# COMM_2022-13-02.net
KiCad netlist of a schematic drawn in Altium Designer
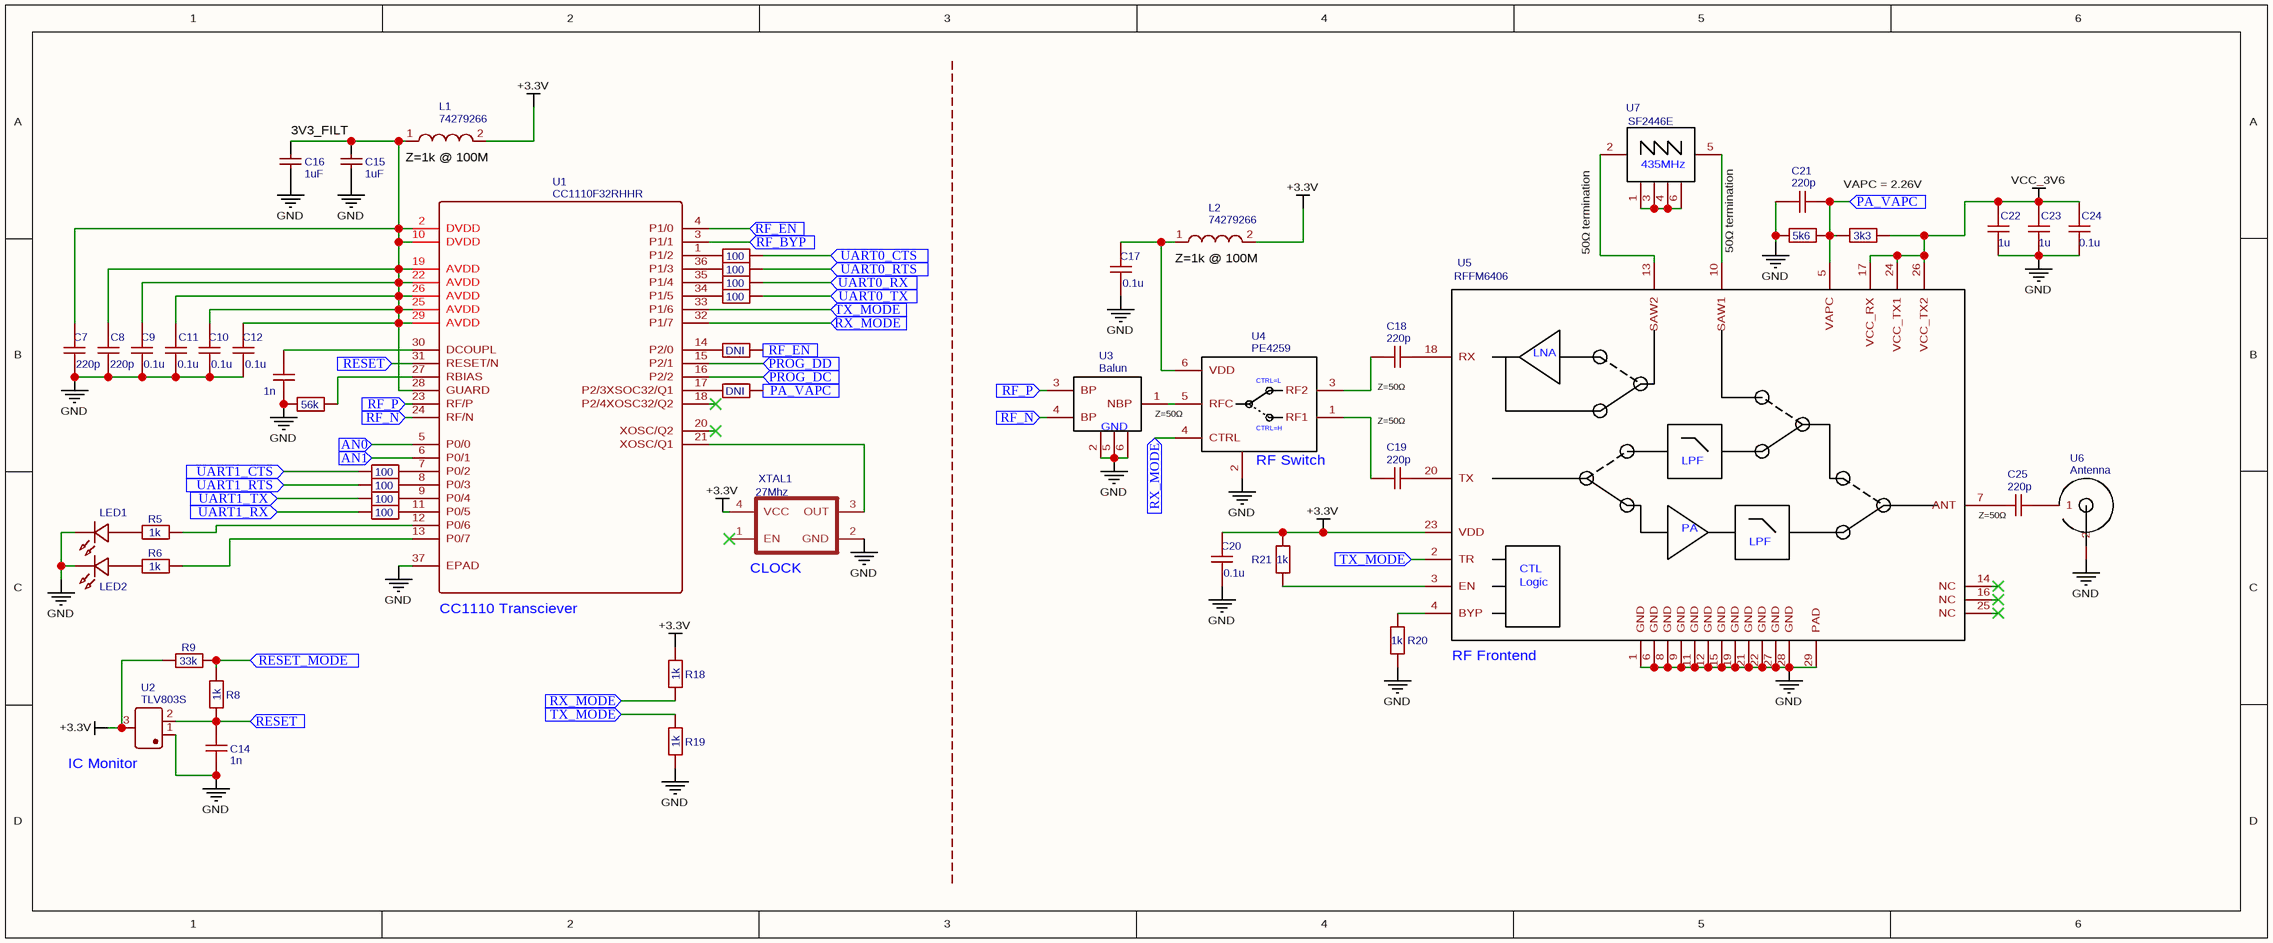
[diagram p0: COMM_2022-13-02.schdoc]

(export (version "E")
  (design (tool "Eeschema 10.0.6"))
  (components
    (comp (ref "C7")
      (value "220p")
      (fields (field (name "CONTRIBUTOR") "LCEDA_Lib"))
      (libsource (lib "altium-import") (part "root_1_220p_"))
    )
    (comp (ref "C8")
      (value "220p")
      (fields (field (name "CONTRIBUTOR") "LCEDA_Lib"))
      (libsource (lib "altium-import") (part "root_1_220p_"))
    )
    (comp (ref "C9")
      (value "0.1u")
      (fields (field (name "CONTRIBUTOR") "LCEDA_Lib"))
      (libsource (lib "altium-import") (part "root_1_0.1u_"))
    )
    (comp (ref "C10")
      (value "0.1u")
      (fields (field (name "CONTRIBUTOR") "LCEDA_Lib"))
      (libsource (lib "altium-import") (part "root_1_0.1u_"))
    )
    (comp (ref "C11")
      (value "0.1u")
      (fields (field (name "CONTRIBUTOR") "LCEDA_Lib"))
      (libsource (lib "altium-import") (part "root_1_0.1u_"))
    )
    (comp (ref "C12")
      (value "0.1u")
      (fields (field (name "CONTRIBUTOR") "LCEDA_Lib"))
      (libsource (lib "altium-import") (part "root_1_0.1u_"))
    )
    (comp (ref "C13")
      (value "1n")
      (fields (field (name "CONTRIBUTOR") "LCEDA_Lib"))
      (libsource (lib "altium-import") (part "root_1_1n_"))
    )
    (comp (ref "C14")
      (value "1n")
      (fields (field (name "CONTRIBUTOR") "LCEDA_Lib"))
      (libsource (lib "altium-import") (part "root_1_1n_"))
    )
    (comp (ref "C15")
      (value "1uF")
      (fields
        (field (name "BOM_SUPPLIER PART") "C444741")
        (field (name "BOM_MANUFACTURER PART") "SR305C105KAR")
        (field (name "CONTRIBUTOR") "LCSC")
      )
      (libsource (lib "altium-import") (part "root_1_1uF_"))
    )
    (comp (ref "C16")
      (value "1uF")
      (fields
        (field (name "BOM_SUPPLIER PART") "C444741")
        (field (name "BOM_MANUFACTURER PART") "SR305C105KAR")
        (field (name "CONTRIBUTOR") "LCSC")
      )
      (libsource (lib "altium-import") (part "root_1_1uF_"))
    )
    (comp (ref "C17")
      (value "0.1u")
      (fields (field (name "CONTRIBUTOR") "LCEDA_Lib"))
      (libsource (lib "altium-import") (part "root_1_0.1u_"))
    )
    (comp (ref "C18")
      (value "220p")
      (fields (field (name "CONTRIBUTOR") "LCEDA_Lib"))
      (libsource (lib "altium-import") (part "root_2_220p_"))
    )
    (comp (ref "C19")
      (value "220p")
      (fields (field (name "CONTRIBUTOR") "LCEDA_Lib"))
      (libsource (lib "altium-import") (part "root_2_220p_"))
    )
    (comp (ref "C20")
      (value "0.1u")
      (fields (field (name "CONTRIBUTOR") "LCEDA_Lib"))
      (libsource (lib "altium-import") (part "root_1_0.1u_"))
    )
    (comp (ref "C21")
      (value "220p")
      (fields (field (name "CONTRIBUTOR") "LCEDA_Lib"))
      (libsource (lib "altium-import") (part "root_2_220p_"))
    )
    (comp (ref "C22")
      (value "1u")
      (fields (field (name "CONTRIBUTOR") "LCEDA_Lib"))
      (libsource (lib "altium-import") (part "root_3_1u_"))
    )
    (comp (ref "C23")
      (value "1u")
      (fields (field (name "CONTRIBUTOR") "LCEDA_Lib"))
      (libsource (lib "altium-import") (part "root_3_1u_"))
    )
    (comp (ref "C24")
      (value "0.1u")
      (fields (field (name "CONTRIBUTOR") "LCEDA_Lib"))
      (libsource (lib "altium-import") (part "root_3_0.1u_"))
    )
    (comp (ref "C25")
      (value "220p")
      (fields (field (name "CONTRIBUTOR") "LCEDA_Lib"))
      (libsource (lib "altium-import") (part "root_2_220p_"))
    )
    (comp (ref "L1")
      (value "74279266")
      (description "SMD EMI Suppression Ferrite Bead WE-CBF, Z")
      (libsource (lib "altium-import") (part "root_0_74279266_"))
    )
    (comp (ref "L2")
      (value "74279266")
      (description "SMD EMI Suppression Ferrite Bead WE-CBF, Z")
      (libsource (lib "altium-import") (part "root_0_74279266_"))
    )
    (comp (ref "LED1")
      (value "LED-TH-3mm_R")
      (fields
        (field (name "BOM_MANUFACTURER PART") "204-10SDRD/S530-A3-L")
        (field (name "BOM_SUPPLIER PART") "C84774")
        (field (name "CONTRIBUTOR") "LCEDA_Lib")
      )
      (libsource (lib "altium-import") (part "root_2_LED-TH-3mm_R_"))
    )
    (comp (ref "LED2")
      (value "LED-TH-3mm_R")
      (fields
        (field (name "BOM_MANUFACTURER PART") "204-10SDRD/S530-A3-L")
        (field (name "BOM_SUPPLIER PART") "C84774")
        (field (name "CONTRIBUTOR") "LCEDA_Lib")
      )
      (libsource (lib "altium-import") (part "root_2_LED-TH-3mm_R_"))
    )
    (comp (ref "R3")
      (value "DNI")
      (fields (field (name "CONTRIBUTOR") "LCEDA_Lib"))
      (libsource (lib "altium-import") (part "root_0_DNI_"))
    )
    (comp (ref "R4")
      (value "DNI")
      (fields (field (name "CONTRIBUTOR") "LCEDA_Lib"))
      (libsource (lib "altium-import") (part "root_0_DNI_"))
    )
    (comp (ref "R5")
      (value "1k")
      (fields (field (name "CONTRIBUTOR") "LCEDA_Lib"))
      (libsource (lib "altium-import") (part "root_0_1k_"))
    )
    (comp (ref "R6")
      (value "1k")
      (fields (field (name "CONTRIBUTOR") "LCEDA_Lib"))
      (libsource (lib "altium-import") (part "root_0_1k_"))
    )
    (comp (ref "R7")
      (value "56k")
      (fields (field (name "CONTRIBUTOR") "LCEDA_Lib"))
      (libsource (lib "altium-import") (part "root_2_56k_"))
    )
    (comp (ref "R8")
      (value "1k")
      (fields (field (name "CONTRIBUTOR") "LCEDA_Lib"))
      (libsource (lib "altium-import") (part "root_1_1k_"))
    )
    (comp (ref "R9")
      (value "33k")
      (fields (field (name "CONTRIBUTOR") "LCEDA_Lib"))
      (libsource (lib "altium-import") (part "root_2_33k_"))
    )
    (comp (ref "R10")
      (value "100")
      (fields (field (name "CONTRIBUTOR") "LCEDA_Lib"))
      (libsource (lib "altium-import") (part "root_0_100_"))
    )
    (comp (ref "R11")
      (value "100")
      (fields (field (name "CONTRIBUTOR") "LCEDA_Lib"))
      (libsource (lib "altium-import") (part "root_0_100_"))
    )
    (comp (ref "R12")
      (value "100")
      (fields (field (name "CONTRIBUTOR") "LCEDA_Lib"))
      (libsource (lib "altium-import") (part "root_0_100_"))
    )
    (comp (ref "R13")
      (value "100")
      (fields (field (name "CONTRIBUTOR") "LCEDA_Lib"))
      (libsource (lib "altium-import") (part "root_0_100_"))
    )
    (comp (ref "R14")
      (value "100")
      (fields (field (name "CONTRIBUTOR") "LCEDA_Lib"))
      (libsource (lib "altium-import") (part "root_0_100_"))
    )
    (comp (ref "R15")
      (value "100")
      (fields (field (name "CONTRIBUTOR") "LCEDA_Lib"))
      (libsource (lib "altium-import") (part "root_0_100_"))
    )
    (comp (ref "R16")
      (value "100")
      (fields (field (name "CONTRIBUTOR") "LCEDA_Lib"))
      (libsource (lib "altium-import") (part "root_0_100_"))
    )
    (comp (ref "R17")
      (value "100")
      (fields (field (name "CONTRIBUTOR") "LCEDA_Lib"))
      (libsource (lib "altium-import") (part "root_0_100_"))
    )
    (comp (ref "R18")
      (value "1k")
      (fields (field (name "CONTRIBUTOR") "LCEDA_Lib"))
      (libsource (lib "altium-import") (part "root_1_1k_"))
    )
    (comp (ref "R19")
      (value "1k")
      (fields (field (name "CONTRIBUTOR") "LCEDA_Lib"))
      (libsource (lib "altium-import") (part "root_1_1k_"))
    )
    (comp (ref "R20")
      (value "1k")
      (fields (field (name "CONTRIBUTOR") "LCEDA_Lib"))
      (libsource (lib "altium-import") (part "root_1_1k_"))
    )
    (comp (ref "R21")
      (value "1k")
      (fields (field (name "CONTRIBUTOR") "LCEDA_Lib"))
      (libsource (lib "altium-import") (part "root_3_1k_"))
    )
    (comp (ref "R22")
      (value "5k6")
      (fields (field (name "CONTRIBUTOR") "LCEDA_Lib"))
      (libsource (lib "altium-import") (part "root_2_5k6_"))
    )
    (comp (ref "R23")
      (value "3k3")
      (fields (field (name "CONTRIBUTOR") "LCEDA_Lib"))
      (libsource (lib "altium-import") (part "root_2_3k3_"))
    )
    (comp (ref "U1")
      (value "CC1110F32RHHR")
      (fields (field (name "BOM_SUPPLIER PART") "C117000") (field (name "CONTRIBUTOR") "LCSC"))
      (libsource (lib "altium-import") (part "root_0_CC1110F32RHHR_"))
    )
    (comp (ref "U2") (value "TLV803S") (libsource (lib "altium-import") (part "root_2_TLV803S_")))
    (comp (ref "U3")
      (value "Balun")
      (fields (field (name "BOM_MANUFACTURER PART") "0433BM15A0001E") (field (name "CONTRIBUTOR") "Arteen"))
      (libsource (lib "altium-import") (part "root_0_Balun_"))
    )
    (comp (ref "U4")
      (value "PE4259")
      (fields (field (name "CONTRIBUTOR") "IntenseFence1"))
      (libsource (lib "altium-import") (part "root_0_PE4259_"))
    )
    (comp (ref "U5")
      (value "RFFM6406")
      (fields (field (name "CONTRIBUTOR") "IntenseFence1"))
      (libsource (lib "altium-import") (part "root_0_RFFM6406_"))
    )
    (comp (ref "U6")
      (value "Antenna")
      (fields (field (name "CONTRIBUTOR") "Arteen"))
      (libsource (lib "altium-import") (part "root_0_Antenna_"))
    )
    (comp (ref "U7")
      (value "SF2446E")
      (fields (field (name "CONTRIBUTOR") "Arteen"))
      (libsource (lib "altium-import") (part "root_0_SF2446E_"))
    )
    (comp (ref "XTAL1")
      (value "27Mhz")
      (fields (field (name "CONTRIBUTOR") "DangerousPrototype"))
      (libsource (lib "altium-import") (part "root_0_27Mhz_"))
    )
  )
  (nets
    (net (code "1") (name "+3.3V") (class "Default")
      (node (ref "C20") (pin "2") (pinfunction "2_2") (pintype "passive"))
      (node (ref "L1") (pin "2") (pinfunction "2_2") (pintype "passive"))
      (node (ref "L2") (pin "2") (pinfunction "2_2") (pintype "passive"))
      (node (ref "R18") (pin "2") (pinfunction "2_2") (pintype "passive"))
      (node (ref "R21") (pin "1") (pinfunction "1_1") (pintype "passive"))
      (node (ref "R9") (pin "2") (pinfunction "2_2") (pintype "passive"))
      (node (ref "U2") (pin "3") (pinfunction "3_3") (pintype "passive"))
      (node (ref "U5") (pin "23") (pinfunction "VDD_23") (pintype "passive"))
      (node (ref "XTAL1") (pin "4") (pinfunction "VCC_4") (pintype "passive"))
    )
    (net (code "2") (name "/AN0") (class "Default")
      (node (ref "U1") (pin "5") (pinfunction "P0/0_5") (pintype "passive"))
    )
    (net (code "3") (name "/AN1") (class "Default")
      (node (ref "U1") (pin "6") (pinfunction "P0/1_6") (pintype "passive"))
    )
    (net (code "4") (name "/PA_VAPC") (class "Default")
      (node (ref "C21") (pin "1") (pinfunction "1_1") (pintype "passive"))
      (node (ref "R22") (pin "1") (pinfunction "1_1") (pintype "passive"))
      (node (ref "R23") (pin "2") (pinfunction "2_2") (pintype "passive"))
      (node (ref "R4") (pin "2") (pinfunction "2_2") (pintype "passive"))
      (node (ref "U5") (pin "5") (pinfunction "VAPC_5") (pintype "passive"))
    )
    (net (code "5") (name "/PROG_DC") (class "Default")
      (node (ref "U1") (pin "16") (pinfunction "P2/2_16") (pintype "passive"))
    )
    (net (code "6") (name "/PROG_DD") (class "Default")
      (node (ref "U1") (pin "15") (pinfunction "P2/1_15") (pintype "passive"))
    )
    (net (code "7") (name "/RESET") (class "Default")
      (node (ref "C14") (pin "2") (pinfunction "2_2") (pintype "passive"))
      (node (ref "R8") (pin "1") (pinfunction "1_1") (pintype "passive"))
      (node (ref "U1") (pin "31") (pinfunction "RESET/N_31") (pintype "passive"))
      (node (ref "U2") (pin "2") (pinfunction "2_2") (pintype "passive"))
    )
    (net (code "8") (name "/RESET_MODE") (class "Default")
      (node (ref "R8") (pin "2") (pinfunction "2_2") (pintype "passive"))
      (node (ref "R9") (pin "1") (pinfunction "1_1") (pintype "passive"))
    )
    (net (code "9") (name "/RF_BYP") (class "Default")
      (node (ref "U1") (pin "3") (pinfunction "P1/1_3") (pintype "passive"))
    )
    (net (code "10") (name "/RF_EN") (class "Default")
      (node (ref "R3") (pin "2") (pinfunction "2_2") (pintype "passive"))
      (node (ref "U1") (pin "4") (pinfunction "P1/0_4") (pintype "passive"))
    )
    (net (code "11") (name "/RF_N") (class "Default")
      (node (ref "U1") (pin "24") (pinfunction "RF/N_24") (pintype "passive"))
      (node (ref "U3") (pin "4") (pinfunction "BP_4") (pintype "passive"))
    )
    (net (code "12") (name "/RF_P") (class "Default")
      (node (ref "U1") (pin "23") (pinfunction "RF/P_23") (pintype "passive"))
      (node (ref "U3") (pin "3") (pinfunction "BP_3") (pintype "passive"))
    )
    (net (code "13") (name "/RX_MODE") (class "Default")
      (node (ref "R18") (pin "1") (pinfunction "1_1") (pintype "passive"))
      (node (ref "U1") (pin "32") (pinfunction "P1/7_32") (pintype "passive"))
      (node (ref "U4") (pin "4") (pinfunction "CTRL_4") (pintype "passive"))
    )
    (net (code "14") (name "/TX_MODE") (class "Default")
      (node (ref "R19") (pin "2") (pinfunction "2_2") (pintype "passive"))
      (node (ref "U1") (pin "33") (pinfunction "P1/6_33") (pintype "passive"))
      (node (ref "U5") (pin "2") (pinfunction "TR_2") (pintype "passive"))
    )
    (net (code "15") (name "/UART0_CTS") (class "Default")
      (node (ref "R17") (pin "2") (pinfunction "2_2") (pintype "passive"))
    )
    (net (code "16") (name "/UART0_RTS") (class "Default")
      (node (ref "R16") (pin "2") (pinfunction "2_2") (pintype "passive"))
    )
    (net (code "17") (name "/UART0_RX") (class "Default")
      (node (ref "R15") (pin "2") (pinfunction "2_2") (pintype "passive"))
    )
    (net (code "18") (name "/UART0_TX") (class "Default")
      (node (ref "R14") (pin "2") (pinfunction "2_2") (pintype "passive"))
    )
    (net (code "19") (name "/UART1_CTS") (class "Default")
      (node (ref "R10") (pin "1") (pinfunction "1_1") (pintype "passive"))
    )
    (net (code "20") (name "/UART1_RTS") (class "Default")
      (node (ref "R11") (pin "1") (pinfunction "1_1") (pintype "passive"))
    )
    (net (code "21") (name "/UART1_RX") (class "Default")
      (node (ref "R13") (pin "1") (pinfunction "1_1") (pintype "passive"))
    )
    (net (code "22") (name "/UART1_TX") (class "Default")
      (node (ref "R12") (pin "1") (pinfunction "1_1") (pintype "passive"))
    )
    (net (code "23") (name "GND") (class "Default")
      (node (ref "C10") (pin "1") (pinfunction "1_1") (pintype "passive"))
      (node (ref "C11") (pin "1") (pinfunction "1_1") (pintype "passive"))
      (node (ref "C12") (pin "1") (pinfunction "1_1") (pintype "passive"))
      (node (ref "C13") (pin "1") (pinfunction "1_1") (pintype "passive"))
      (node (ref "C14") (pin "1") (pinfunction "1_1") (pintype "passive"))
      (node (ref "C15") (pin "1") (pinfunction "1_1") (pintype "passive"))
      (node (ref "C16") (pin "1") (pinfunction "1_1") (pintype "passive"))
      (node (ref "C17") (pin "1") (pinfunction "1_1") (pintype "passive"))
      (node (ref "C20") (pin "1") (pinfunction "1_1") (pintype "passive"))
      (node (ref "C21") (pin "2") (pinfunction "2_2") (pintype "passive"))
      (node (ref "C22") (pin "2") (pinfunction "2_2") (pintype "passive"))
      (node (ref "C23") (pin "2") (pinfunction "2_2") (pintype "passive"))
      (node (ref "C24") (pin "2") (pinfunction "2_2") (pintype "passive"))
      (node (ref "C7") (pin "1") (pinfunction "1_1") (pintype "passive"))
      (node (ref "C8") (pin "1") (pinfunction "1_1") (pintype "passive"))
      (node (ref "C9") (pin "1") (pinfunction "1_1") (pintype "passive"))
      (node (ref "LED1") (pin "2") (pinfunction "2_2") (pintype "passive"))
      (node (ref "LED2") (pin "2") (pinfunction "2_2") (pintype "passive"))
      (node (ref "R19") (pin "1") (pinfunction "1_1") (pintype "passive"))
      (node (ref "R20") (pin "1") (pinfunction "1_1") (pintype "passive"))
      (node (ref "R22") (pin "2") (pinfunction "2_2") (pintype "passive"))
      (node (ref "R7") (pin "2") (pinfunction "2_2") (pintype "passive"))
      (node (ref "U1") (pin "37") (pinfunction "EPAD_37") (pintype "passive"))
      (node (ref "U2") (pin "1") (pinfunction "1_1") (pintype "passive"))
      (node (ref "U3") (pin "2") (pinfunction "GND_2") (pintype "passive"))
      (node (ref "U3") (pin "5") (pinfunction "GND_5") (pintype "passive"))
      (node (ref "U3") (pin "6") (pinfunction "GND_6") (pintype "passive"))
      (node (ref "U4") (pin "2") (pinfunction "GND_2") (pintype "passive"))
      (node (ref "U5") (pin "1") (pinfunction "GND_1") (pintype "passive"))
      (node (ref "U5") (pin "11") (pinfunction "GND_11") (pintype "passive"))
      (node (ref "U5") (pin "12") (pinfunction "GND_12") (pintype "passive"))
      (node (ref "U5") (pin "15") (pinfunction "GND_15") (pintype "passive"))
      (node (ref "U5") (pin "19") (pinfunction "GND_19") (pintype "passive"))
      (node (ref "U5") (pin "21") (pinfunction "GND_21") (pintype "passive"))
      (node (ref "U5") (pin "22") (pinfunction "GND_22") (pintype "passive"))
      (node (ref "U5") (pin "27") (pinfunction "GND_27") (pintype "passive"))
      (node (ref "U5") (pin "28") (pinfunction "GND_28") (pintype "passive"))
      (node (ref "U5") (pin "29") (pinfunction "PAD_29") (pintype "passive"))
      (node (ref "U5") (pin "6") (pinfunction "GND_6") (pintype "passive"))
      (node (ref "U5") (pin "8") (pinfunction "GND_8") (pintype "passive"))
      (node (ref "U5") (pin "9") (pinfunction "GND_9") (pintype "passive"))
      (node (ref "U6") (pin "2") (pinfunction "2_2") (pintype "passive"))
      (node (ref "XTAL1") (pin "2") (pinfunction "GND_2") (pintype "passive"))
    )
    (net (code "24") (name "Net-(C25-Pad1)") (class "Default")
      (node (ref "C25") (pin "1") (pinfunction "1_1") (pintype "passive"))
      (node (ref "U6") (pin "1") (pinfunction "1_1") (pintype "passive"))
    )
    (net (code "25") (name "Net-(LED1-Pad1)") (class "Default")
      (node (ref "LED1") (pin "1") (pinfunction "1_1") (pintype "passive"))
      (node (ref "R5") (pin "1") (pinfunction "1_1") (pintype "passive"))
    )
    (net (code "26") (name "Net-(LED2-Pad1)") (class "Default")
      (node (ref "LED2") (pin "1") (pinfunction "1_1") (pintype "passive"))
      (node (ref "R6") (pin "1") (pinfunction "1_1") (pintype "passive"))
    )
    (net (code "27") (name "Net-(U1-DCOUPL)") (class "Default")
      (node (ref "C13") (pin "2") (pinfunction "2_2") (pintype "passive"))
      (node (ref "U1") (pin "30") (pinfunction "DCOUPL_30") (pintype "passive"))
    )
    (net (code "28") (name "Net-(U1-GUARD)") (class "Default")
      (node (ref "C10") (pin "2") (pinfunction "2_2") (pintype "passive"))
      (node (ref "C11") (pin "2") (pinfunction "2_2") (pintype "passive"))
      (node (ref "C12") (pin "2") (pinfunction "2_2") (pintype "passive"))
      (node (ref "C15") (pin "2") (pinfunction "2_2") (pintype "passive"))
      (node (ref "C16") (pin "2") (pinfunction "2_2") (pintype "passive"))
      (node (ref "C7") (pin "2") (pinfunction "2_2") (pintype "passive"))
      (node (ref "C8") (pin "2") (pinfunction "2_2") (pintype "passive"))
      (node (ref "C9") (pin "2") (pinfunction "2_2") (pintype "passive"))
      (node (ref "L1") (pin "1") (pinfunction "1_1") (pintype "passive"))
      (node (ref "U1") (pin "10") (pinfunction "DVDD_10") (pintype "passive"))
      (node (ref "U1") (pin "19") (pinfunction "AVDD_19") (pintype "passive"))
      (node (ref "U1") (pin "2") (pinfunction "DVDD_2") (pintype "passive"))
      (node (ref "U1") (pin "22") (pinfunction "AVDD_22") (pintype "passive"))
      (node (ref "U1") (pin "25") (pinfunction "AVDD_25") (pintype "passive"))
      (node (ref "U1") (pin "26") (pinfunction "AVDD_26") (pintype "passive"))
      (node (ref "U1") (pin "28") (pinfunction "GUARD_28") (pintype "passive"))
      (node (ref "U1") (pin "29") (pinfunction "AVDD_29") (pintype "passive"))
    )
    (net (code "29") (name "Net-(U1-P0{slash}2)") (class "Default")
      (node (ref "R10") (pin "2") (pinfunction "2_2") (pintype "passive"))
      (node (ref "U1") (pin "7") (pinfunction "P0/2_7") (pintype "passive"))
    )
    (net (code "30") (name "Net-(U1-P0{slash}3)") (class "Default")
      (node (ref "R11") (pin "2") (pinfunction "2_2") (pintype "passive"))
      (node (ref "U1") (pin "8") (pinfunction "P0/3_8") (pintype "passive"))
    )
    (net (code "31") (name "Net-(U1-P0{slash}4)") (class "Default")
      (node (ref "R12") (pin "2") (pinfunction "2_2") (pintype "passive"))
      (node (ref "U1") (pin "9") (pinfunction "P0/4_9") (pintype "passive"))
    )
    (net (code "32") (name "Net-(U1-P0{slash}5)") (class "Default")
      (node (ref "R13") (pin "2") (pinfunction "2_2") (pintype "passive"))
      (node (ref "U1") (pin "11") (pinfunction "P0/5_11") (pintype "passive"))
    )
    (net (code "33") (name "Net-(U1-P0{slash}6)") (class "Default")
      (node (ref "R5") (pin "2") (pinfunction "2_2") (pintype "passive"))
      (node (ref "U1") (pin "12") (pinfunction "P0/6_12") (pintype "passive"))
    )
    (net (code "34") (name "Net-(U1-P0{slash}7)") (class "Default")
      (node (ref "R6") (pin "2") (pinfunction "2_2") (pintype "passive"))
      (node (ref "U1") (pin "13") (pinfunction "P0/7_13") (pintype "passive"))
    )
    (net (code "35") (name "Net-(U1-P1{slash}2)") (class "Default")
      (node (ref "R17") (pin "1") (pinfunction "1_1") (pintype "passive"))
      (node (ref "U1") (pin "1") (pinfunction "P1/2_1") (pintype "passive"))
    )
    (net (code "36") (name "Net-(U1-P1{slash}3)") (class "Default")
      (node (ref "R16") (pin "1") (pinfunction "1_1") (pintype "passive"))
      (node (ref "U1") (pin "36") (pinfunction "P1/3_36") (pintype "passive"))
    )
    (net (code "37") (name "Net-(U1-P1{slash}4)") (class "Default")
      (node (ref "R15") (pin "1") (pinfunction "1_1") (pintype "passive"))
      (node (ref "U1") (pin "35") (pinfunction "P1/4_35") (pintype "passive"))
    )
    (net (code "38") (name "Net-(U1-P1{slash}5)") (class "Default")
      (node (ref "R14") (pin "1") (pinfunction "1_1") (pintype "passive"))
      (node (ref "U1") (pin "34") (pinfunction "P1/5_34") (pintype "passive"))
    )
    (net (code "39") (name "Net-(U1-P2{slash}0)") (class "Default")
      (node (ref "R3") (pin "1") (pinfunction "1_1") (pintype "passive"))
      (node (ref "U1") (pin "14") (pinfunction "P2/0_14") (pintype "passive"))
    )
    (net (code "40") (name "Net-(U1-P2{slash}3XSOC32{slash}Q1)") (class "Default")
      (node (ref "R4") (pin "1") (pinfunction "1_1") (pintype "passive"))
      (node (ref "U1") (pin "17") (pinfunction "P2/3XSOC32/Q1_17") (pintype "passive"))
    )
    (net (code "41") (name "Net-(U1-RBIAS)") (class "Default")
      (node (ref "R7") (pin "1") (pinfunction "1_1") (pintype "passive"))
      (node (ref "U1") (pin "27") (pinfunction "RBIAS_27") (pintype "passive"))
    )
    (net (code "42") (name "Net-(U1-XOSC{slash}Q1)") (class "Default")
      (node (ref "U1") (pin "21") (pinfunction "XOSC/Q1_21") (pintype "passive"))
      (node (ref "XTAL1") (pin "3") (pinfunction "OUT_3") (pintype "passive"))
    )
    (net (code "43") (name "Net-(U3-NBP)") (class "Default")
      (node (ref "U3") (pin "1") (pinfunction "NBP_1") (pintype "passive"))
      (node (ref "U4") (pin "5") (pinfunction "RFC_5") (pintype "passive"))
    )
    (net (code "44") (name "Net-(U4-RF1)") (class "Default")
      (node (ref "C19") (pin "2") (pinfunction "2_2") (pintype "passive"))
      (node (ref "U4") (pin "1") (pinfunction "RF1_1") (pintype "passive"))
    )
    (net (code "45") (name "Net-(U4-RF2)") (class "Default")
      (node (ref "C18") (pin "2") (pinfunction "2_2") (pintype "passive"))
      (node (ref "U4") (pin "3") (pinfunction "RF2_3") (pintype "passive"))
    )
    (net (code "46") (name "Net-(U4-VDD)") (class "Default")
      (node (ref "C17") (pin "2") (pinfunction "2_2") (pintype "passive"))
      (node (ref "L2") (pin "1") (pinfunction "1_1") (pintype "passive"))
      (node (ref "U4") (pin "6") (pinfunction "VDD_6") (pintype "passive"))
    )
    (net (code "47") (name "Net-(U5-ANT)") (class "Default")
      (node (ref "C25") (pin "2") (pinfunction "2_2") (pintype "passive"))
      (node (ref "U5") (pin "7") (pinfunction "ANT_7") (pintype "passive"))
    )
    (net (code "48") (name "Net-(U5-BYP)") (class "Default")
      (node (ref "R20") (pin "2") (pinfunction "2_2") (pintype "passive"))
      (node (ref "U5") (pin "4") (pinfunction "BYP_4") (pintype "passive"))
    )
    (net (code "49") (name "Net-(U5-EN)") (class "Default")
      (node (ref "R21") (pin "2") (pinfunction "2_2") (pintype "passive"))
      (node (ref "U5") (pin "3") (pinfunction "EN_3") (pintype "passive"))
    )
    (net (code "50") (name "Net-(U5-RX)") (class "Default")
      (node (ref "C18") (pin "1") (pinfunction "1_1") (pintype "passive"))
      (node (ref "U5") (pin "18") (pinfunction "RX_18") (pintype "passive"))
    )
    (net (code "51") (name "Net-(U5-SAW1)") (class "Default")
      (node (ref "U5") (pin "10") (pinfunction "SAW1_10") (pintype "passive"))
      (node (ref "U7") (pin "5") (pinfunction "5_5") (pintype "passive"))
    )
    (net (code "52") (name "Net-(U5-SAW2)") (class "Default")
      (node (ref "U5") (pin "13") (pinfunction "SAW2_13") (pintype "passive"))
      (node (ref "U7") (pin "2") (pinfunction "2_2") (pintype "passive"))
    )
    (net (code "53") (name "Net-(U5-TX)") (class "Default")
      (node (ref "C19") (pin "1") (pinfunction "1_1") (pintype "passive"))
      (node (ref "U5") (pin "20") (pinfunction "TX_20") (pintype "passive"))
    )
    (net (code "54") (name "Net-(U7-Pad1)") (class "Default")
      (node (ref "U7") (pin "1") (pinfunction "1_1") (pintype "passive"))
      (node (ref "U7") (pin "3") (pinfunction "3_3") (pintype "passive"))
      (node (ref "U7") (pin "4") (pinfunction "4_4") (pintype "passive"))
      (node (ref "U7") (pin "6") (pinfunction "6_6") (pintype "passive"))
    )
    (net (code "55") (name "VCC_3V6") (class "Default")
      (node (ref "C22") (pin "1") (pinfunction "1_1") (pintype "passive"))
      (node (ref "C23") (pin "1") (pinfunction "1_1") (pintype "passive"))
      (node (ref "C24") (pin "1") (pinfunction "1_1") (pintype "passive"))
      (node (ref "R23") (pin "1") (pinfunction "1_1") (pintype "passive"))
      (node (ref "U5") (pin "17") (pinfunction "VCC_RX_17") (pintype "passive"))
      (node (ref "U5") (pin "24") (pinfunction "VCC_TX1_24") (pintype "passive"))
      (node (ref "U5") (pin "26") (pinfunction "VCC_TX2_26") (pintype "passive"))
    )
    (net (code "56") (name "unconnected-(U1-P2{slash}4XOSC32{slash}Q2-Pad18)") (class "Default")
      (node (ref "U1") (pin "18") (pinfunction "P2/4XOSC32/Q2_18") (pintype "passive+no_connect"))
    )
    (net (code "57") (name "unconnected-(U1-XOSC{slash}Q2-Pad20)") (class "Default")
      (node (ref "U1") (pin "20") (pinfunction "XOSC/Q2_20") (pintype "passive+no_connect"))
    )
    (net (code "58") (name "unconnected-(U5-NC-Pad14)") (class "Default")
      (node (ref "U5") (pin "14") (pinfunction "NC_14") (pintype "passive+no_connect"))
    )
    (net (code "59") (name "unconnected-(U5-NC-Pad16)") (class "Default")
      (node (ref "U5") (pin "16") (pinfunction "NC_16") (pintype "passive+no_connect"))
    )
    (net (code "60") (name "unconnected-(U5-NC-Pad25)") (class "Default")
      (node (ref "U5") (pin "25") (pinfunction "NC_25") (pintype "passive+no_connect"))
    )
    (net (code "61") (name "unconnected-(XTAL1-EN-Pad1)") (class "Default")
      (node (ref "XTAL1") (pin "1") (pinfunction "EN_1") (pintype "passive+no_connect"))
    )
  )
)
